# UART.net
KiCad netlist of a schematic drawn in Altium Designer
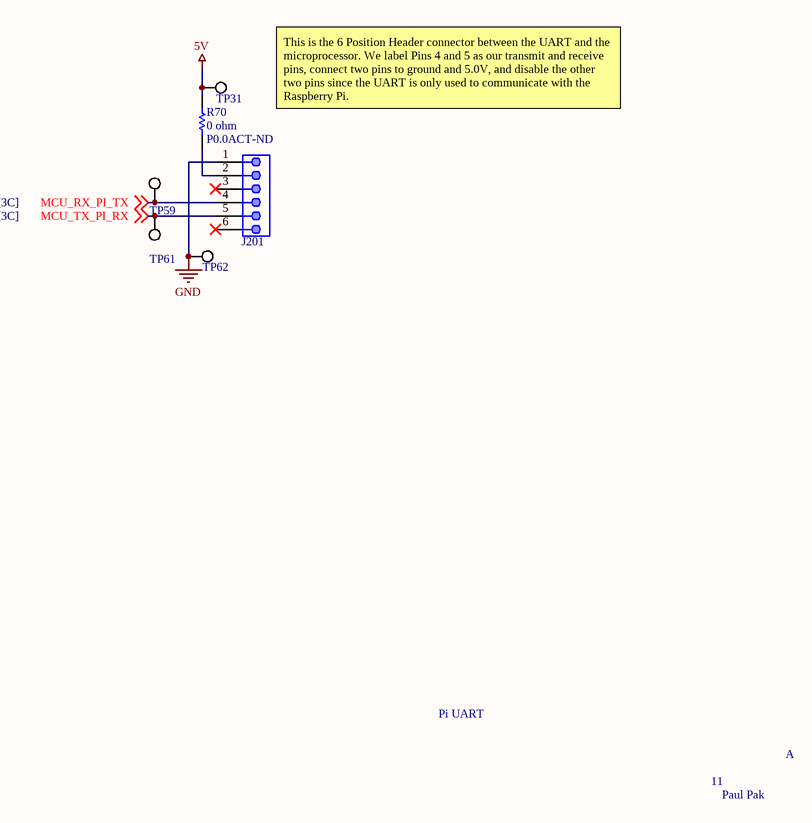
[diagram p0: UART.SchDoc]

(export (version "E")
  (design (tool "Eeschema 10.0.6"))
  (components
    (comp (ref "J201")
      (value "~")
      (footprint "HDR1X6")
      (description "Female, 6C, Rt Angle, .100\"CC; 3.15mm Tail, No Mounting; PBT, Phos. Bronze, 105 C")
      (libsource (lib "Connectors") (part "CONN_HEADER_MALE_1x6"))
    )
    (comp (ref "R70")
      (value "0 ohm")
      (footprint "RESC2013X70X40NL20T20")
      (description "Chip Resistor, 0 Ohm, +/- 1%, 0.125 W, -55 to 155 degC, 0805 (2012 Metric), RoHS, Tape and Reel")
      (fields
        (field (name "PARTNUMBER") "ERJ-6GEY0R00V")
        (field (name "TOLERANCE") "5%")
        (field (name "SUPPLIER PART NUMBER 1") "P0.0ACT-ND")
      )
      (libsource (lib "Altium Content Vault") (part "RES-2"))
    )
    (comp (ref "TP31")
      (value "5019")
      (footprint "KSTN-5019_V")
      (description "Test Point, 1 Position SMD, RoHS, Tape and Reel")
      (fields (field (name "MANUFACTURER") "Keystone Electronics"))
      (libsource (lib "Altium Content Vault") (part "TESTPOINT_WHITE"))
    )
    (comp (ref "TP59")
      (value "5019")
      (footprint "KSTN-5019_V")
      (description "Test Point, 1 Position SMD, RoHS, Tape and Reel")
      (fields (field (name "MANUFACTURER") "Keystone Electronics"))
      (libsource (lib "Altium Content Vault") (part "TESTPOINT_WHITE"))
    )
    (comp (ref "TP61")
      (value "5019")
      (footprint "KSTN-5019_V")
      (description "Test Point, 1 Position SMD, RoHS, Tape and Reel")
      (fields (field (name "MANUFACTURER") "Keystone Electronics"))
      (libsource (lib "Altium Content Vault") (part "TESTPOINT_WHITE"))
    )
    (comp (ref "TP62")
      (value "5019")
      (footprint "KSTN-5019_V")
      (description "Test Point, 1 Position SMD, RoHS, Tape and Reel")
      (fields (field (name "MANUFACTURER") "Keystone Electronics"))
      (libsource (lib "Altium Content Vault") (part "TESTPOINT_WHITE"))
    )
  )
  (nets
    (net (code "1") (name "5V") (class "Default")
      (node (ref "R70") (pin "2") (pinfunction "2_2") (pintype "passive"))
      (node (ref "TP31") (pin "1") (pinfunction "1_1") (pintype "passive"))
    )
    (net (code "2") (name "GND") (class "Default")
      (node (ref "J201") (pin "1") (pinfunction "1_1") (pintype "passive"))
      (node (ref "TP62") (pin "1") (pinfunction "1_1") (pintype "passive"))
    )
    (net (code "3") (name "MCU_RX_PI_TX") (class "Default")
      (node (ref "J201") (pin "4") (pinfunction "4_4") (pintype "passive"))
      (node (ref "TP59") (pin "1") (pinfunction "1_1") (pintype "passive"))
    )
    (net (code "4") (name "MCU_TX_PI_RX") (class "Default")
      (node (ref "J201") (pin "5") (pinfunction "5_5") (pintype "passive"))
      (node (ref "TP61") (pin "1") (pinfunction "1_1") (pintype "passive"))
    )
    (net (code "5") (name "Net-(J201-Pad2)") (class "Default")
      (node (ref "J201") (pin "2") (pinfunction "2_2") (pintype "passive"))
      (node (ref "R70") (pin "1") (pinfunction "1_1") (pintype "passive"))
    )
    (net (code "6") (name "unconnected-(J201-Pad3)") (class "Default")
      (node (ref "J201") (pin "3") (pinfunction "3_3") (pintype "passive+no_connect"))
    )
    (net (code "7") (name "unconnected-(J201-Pad6)") (class "Default")
      (node (ref "J201") (pin "6") (pinfunction "6_6") (pintype "passive+no_connect"))
    )
  )
)
